# 05021002_Analog_s.net
KiCad netlist of a schematic drawn in Altium Designer
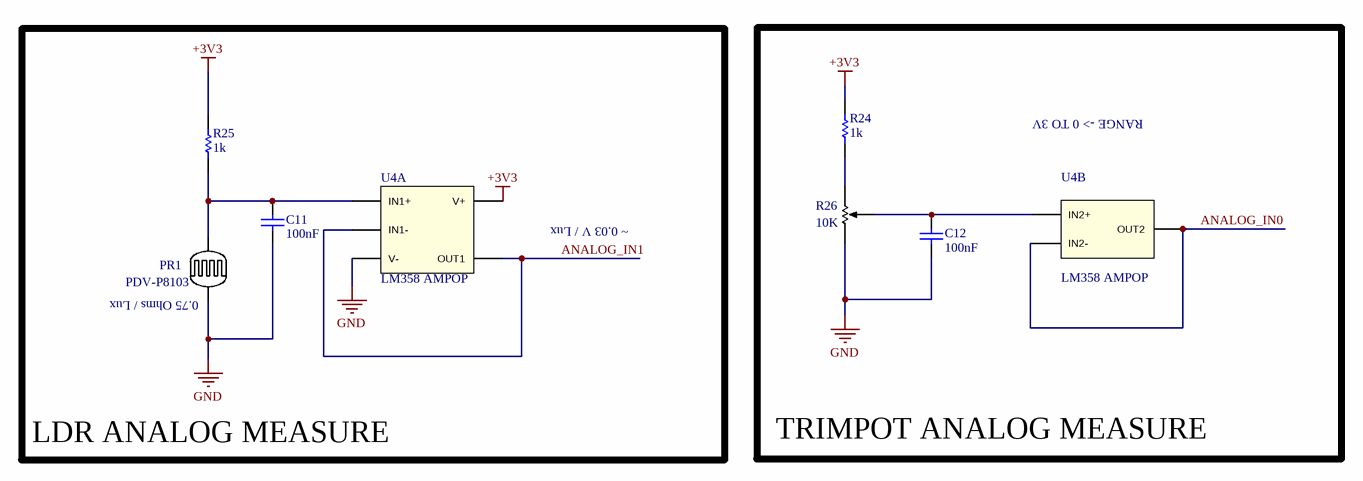
[diagram p0: 05021002_Analog's.SchDoc]

(export (version "E")
  (design (tool "Eeschema 10.0.6"))
  (components
    (comp (ref "C11")
      (value "100nF")
      (footprint "CAPC2012X135N")
      (description "Generic Capacitor")
      (libsource (lib "capacitor_smd_gen") (part "capacitor_gen"))
    )
    (comp (ref "C12")
      (value "100nF")
      (footprint "CAPC2012X135N")
      (description "Generic Capacitor")
      (libsource (lib "capacitor_smd_gen") (part "capacitor_gen"))
    )
    (comp (ref "PR1")
      (value "PDV-P8103")
      (footprint "PDV-P8103")
      (description "Photoconductive photocells designed to sense light from 400 to 700 nm")
      (libsource (lib "IPÊ_BOARD_LIBRARY") (part "PhotoResistor PDV-P8103"))
    )
    (comp (ref "R24")
      (value "1k")
      (footprint "0805")
      (libsource (lib "resistor_smd_gen") (part "resistor_gen"))
    )
    (comp (ref "R25")
      (value "1k")
      (footprint "0805")
      (libsource (lib "resistor_smd_gen") (part "resistor_gen"))
    )
    (comp (ref "R26")
      (value "10K")
      (footprint "TC33X-2-103E")
      (description "3 mm SMD Trimpot® Trimming Potentiometer")
      (libsource (lib "IPÊ_BOARD_LIBRARY") (part "Trimmer 10K"))
    )
    (comp (ref "U4")
      (value "LM358 AMPOP")
      (footprint "SOIC 8")
      (description "OPERATIONAL AMPLIFIER LM358")
      (libsource (lib "PROJETO_KOTAPRESS2016") (part "LM358"))
    )
  )
  (nets
    (net (code "1") (name "+3V3") (class "Default")
      (node (ref "R24") (pin "2") (pinfunction "2_2") (pintype "passive"))
      (node (ref "R25") (pin "2") (pinfunction "2_2") (pintype "passive"))
      (node (ref "U4") (pin "8") (pinfunction "V+_8") (pintype "passive"))
    )
    (net (code "2") (name "/ANALOG_IN0") (class "Default")
      (node (ref "U4") (pin "6") (pinfunction "IN2-_6") (pintype "passive"))
      (node (ref "U4") (pin "7") (pinfunction "OUT2_7") (pintype "passive"))
    )
    (net (code "3") (name "/ANALOG_IN1") (class "Default")
      (node (ref "U4") (pin "1") (pinfunction "OUT1_1") (pintype "passive"))
      (node (ref "U4") (pin "2") (pinfunction "IN1-_2") (pintype "passive"))
    )
    (net (code "4") (name "GND") (class "Default")
      (node (ref "C11") (pin "1") (pinfunction "1_1") (pintype "passive"))
      (node (ref "C12") (pin "1") (pinfunction "1_1") (pintype "passive"))
      (node (ref "PR1") (pin "2") (pinfunction "2_2") (pintype "passive"))
      (node (ref "R26") (pin "1") (pinfunction "CCW_1") (pintype "passive"))
      (node (ref "U4") (pin "4") (pinfunction "V-_4") (pintype "passive"))
    )
    (net (code "5") (name "Net-(R26-CW)") (class "Default")
      (node (ref "R24") (pin "1") (pinfunction "1_1") (pintype "passive"))
      (node (ref "R26") (pin "3") (pinfunction "CW_3") (pintype "passive"))
    )
    (net (code "6") (name "Net-(R26-WIPER)") (class "Default")
      (node (ref "C12") (pin "2") (pinfunction "2_2") (pintype "passive"))
      (node (ref "R26") (pin "2") (pinfunction "WIPER_2") (pintype "passive"))
      (node (ref "U4") (pin "5") (pinfunction "IN2+_5") (pintype "passive"))
    )
    (net (code "7") (name "Net-(U4A-IN1+)") (class "Default")
      (node (ref "C11") (pin "2") (pinfunction "2_2") (pintype "passive"))
      (node (ref "PR1") (pin "1") (pinfunction "1_1") (pintype "passive"))
      (node (ref "R25") (pin "1") (pinfunction "1_1") (pintype "passive"))
      (node (ref "U4") (pin "3") (pinfunction "IN1+_3") (pintype "passive"))
    )
  )
)
